# power1.net
KiCad netlist of a schematic drawn in Altium Designer
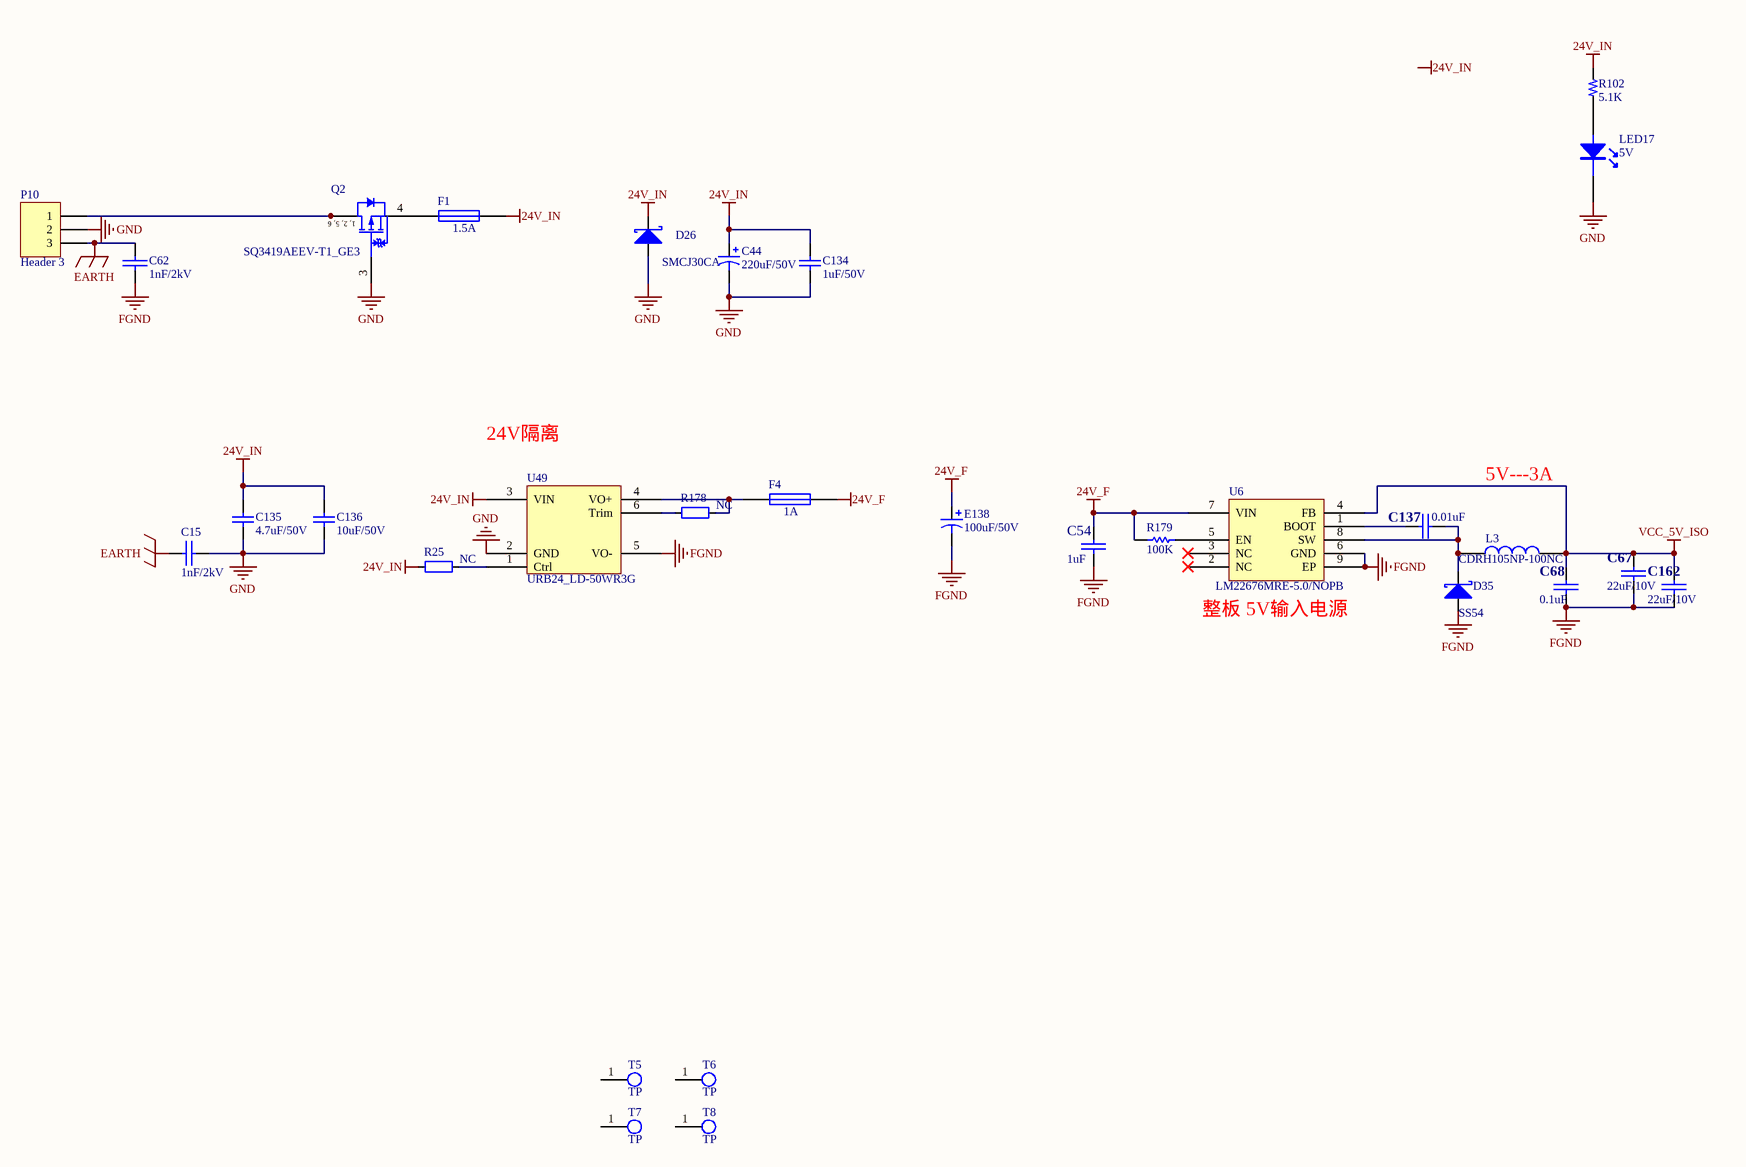
[diagram p0: power1.SchDoc]

(export (version "E")
  (design (tool "Eeschema 10.0.6"))
  (components
    (comp (ref "C15")
      (value "1nF/2kV")
      (footprint "1206C")
      (description "Capacitor")
      (libsource (lib "*") (part "CAP"))
    )
    (comp (ref "C44")
      (value "220uF/50V")
      (footprint "Φ10×10")
      (description "Polarized Capacitor (Radial)")
      (fields (field (name "PUBLISHER") "Altium Limited"))
      (libsource (lib "Miscellaneous Devices") (part "Cap Pol1"))
    )
    (comp (ref "C54")
      (value "1uF")
      (footprint "0603C")
      (description "Capacitor")
      (libsource (lib "*") (part "CAP"))
    )
    (comp (ref "C62")
      (value "1nF/2kV")
      (footprint "1206C")
      (description "Capacitor")
      (libsource (lib "*") (part "CAP"))
    )
    (comp (ref "C67")
      (value "22uF/10V")
      (footprint "1210C")
      (description "Capacitor")
      (libsource (lib "*") (part "CAP"))
    )
    (comp (ref "C68")
      (value "0.1uF")
      (footprint "0603C")
      (description "Capacitor")
      (libsource (lib "*") (part "CAP"))
    )
    (comp (ref "C134")
      (value "1uF/50V")
      (footprint "1210C")
      (description "Capacitor")
      (fields (field (name "PUBLISHER") "Altium Limited"))
      (libsource (lib "Miscellaneous Devices") (part "Cap"))
    )
    (comp (ref "C135")
      (value "4.7uF/50V")
      (footprint "1210C")
      (description "Capacitor")
      (fields (field (name "PUBLISHER") "Altium Limited"))
      (libsource (lib "Miscellaneous Devices") (part "Cap"))
    )
    (comp (ref "C136")
      (value "10uF/50V")
      (footprint "1210C")
      (description "Capacitor")
      (fields (field (name "PUBLISHER") "Altium Limited"))
      (libsource (lib "Miscellaneous Devices") (part "Cap"))
    )
    (comp (ref "C137")
      (value "0.01uF")
      (footprint "0603C")
      (description "Capacitor")
      (libsource (lib "*") (part "CAP"))
    )
    (comp (ref "C162")
      (value "22uF/10V")
      (footprint "1210C")
      (description "Capacitor")
      (libsource (lib "*") (part "CAP"))
    )
    (comp (ref "D26")
      (value "SMCJ30CA")
      (footprint "SMC")
      (description "Schottky Diode")
      (libsource (lib "*") (part "DIODE S"))
    )
    (comp (ref "D35")
      (value "SS54")
      (footprint "SMC")
      (description "Schottky Diode")
      (libsource (lib "*") (part "DIODE S"))
    )
    (comp (ref "E138")
      (value "100uF/50V")
      (footprint "Φ10×10")
      (description "Polarized Capacitor (Radial)")
      (fields (field (name "PUBLISHER") "Altium Limited"))
      (libsource (lib "Miscellaneous Devices") (part "Cap Pol1"))
    )
    (comp (ref "F1")
      (value "1.5A")
      (footprint "1812-F")
      (description "Fuse")
      (fields (field (name "PUBLISHER") "Altium Limited"))
      (libsource (lib "Miscellaneous Devices") (part "Fuse 1"))
    )
    (comp (ref "F4")
      (value "1A")
      (footprint "1812-F")
      (description "Fuse")
      (fields (field (name "PUBLISHER") "Altium Limited"))
      (libsource (lib "Miscellaneous Devices") (part "Fuse 1"))
    )
    (comp (ref "L3") (value "CDRH105NP-100NC") (footprint "CDRH105") (libsource (lib "*") (part "INDUCTOR")))
    (comp (ref "LED17") (value "5V") (footprint "0603LED") (libsource (lib "*") (part "LED")))
    (comp (ref "P10")
      (value "Header 3")
      (footprint "2ETYR-5.08-03P-14-100")
      (description "Header, 3-Pin")
      (fields (field (name "PUBLISHER") "Altium Limited"))
      (libsource (lib "Miscellaneous Connectors") (part "Header 3"))
    )
    (comp (ref "Q2")
      (value "SQ3419AEEV-T1_GE3")
      (footprint "VISH-TSOP-6_V")
      (description "Automotive P-Channel MOSFET, 6.9 A, 40 V, -55 to 175 degC, 6-Pin TSOP, RoHS, Tape and Reel")
      (fields (field (name "MANUFACTURER") "International Rectifier"))
      (libsource (lib "Bogen") (part "SQ3419AEEV-T1_GE3"))
    )
    (comp (ref "R25") (value "NC") (footprint "0603r") (libsource (lib "RC_M_D_00") (part "RES0603")))
    (comp (ref "R102")
      (value "5.1K")
      (footprint "0603R")
      (description "R")
      (libsource (lib "JRJ_1") (part "R"))
    )
    (comp (ref "R178") (value "NC") (footprint "0603r") (libsource (lib "RC_M_D_00") (part "RES0603")))
    (comp (ref "R179")
      (value "100K")
      (footprint "0603R")
      (description "Resistor")
      (fields (field (name "PUBLISHER") "Altium Limited"))
      (libsource (lib "Miscellaneous Devices") (part "Res1"))
    )
    (comp (ref "T5") (value "TP") (footprint "m2.5") (libsource (lib "Schlib_20110825") (part "TP")))
    (comp (ref "T6") (value "TP") (footprint "m2.5") (libsource (lib "Schlib_20110825") (part "TP")))
    (comp (ref "T7") (value "TP") (footprint "m2.5") (libsource (lib "Schlib_20110825") (part "TP")))
    (comp (ref "T8") (value "TP") (footprint "m2.5") (libsource (lib "Schlib_20110825") (part "TP")))
    (comp (ref "U6")
      (value "LM22676MRE-5.0/NOPB")
      (footprint "SOP127P600X168_HS-8N")
      (libsource (lib "Schlib1") (part "LM22676MR-5.0"))
    )
    (comp (ref "U49")
      (value "URB24_LD-50WR3G")
      (footprint "URB24_LD-50WR3G")
      (libsource (lib "Schlib1") (part "URB24_LD-50WR3G"))
    )
  )
  (nets
    (net (code "1") (name "24V_F") (class "Default")
      (node (ref "C54") (pin "2") (pinfunction "2_2") (pintype "passive"))
      (node (ref "E138") (pin "1") (pinfunction "1_1") (pintype "passive"))
      (node (ref "F4") (pin "2") (pinfunction "2_2") (pintype "passive"))
      (node (ref "R179") (pin "2") (pinfunction "2_2") (pintype "passive"))
      (node (ref "U6") (pin "7") (pinfunction "VIN_7") (pintype "passive"))
    )
    (net (code "2") (name "24V_IN") (class "Default")
      (node (ref "C134") (pin "2") (pinfunction "2_2") (pintype "passive"))
      (node (ref "C135") (pin "2") (pinfunction "2_2") (pintype "passive"))
      (node (ref "C136") (pin "2") (pinfunction "2_2") (pintype "passive"))
      (node (ref "C44") (pin "1") (pinfunction "1_1") (pintype "passive"))
      (node (ref "D26") (pin "2") (pinfunction "K_2") (pintype "passive"))
      (node (ref "F1") (pin "2") (pinfunction "2_2") (pintype "passive"))
      (node (ref "R102") (pin "2") (pintype "passive"))
      (node (ref "R25") (pin "1") (pinfunction "1_1") (pintype "passive"))
      (node (ref "U49") (pin "3") (pinfunction "VIN_3") (pintype "passive"))
    )
    (net (code "3") (name "EARTH") (class "Default")
      (node (ref "C15") (pin "2") (pinfunction "2_2") (pintype "passive"))
      (node (ref "C62") (pin "2") (pinfunction "2_2") (pintype "passive"))
      (node (ref "P10") (pin "3") (pinfunction "3_3") (pintype "passive"))
    )
    (net (code "4") (name "FGND") (class "Default")
      (node (ref "C162") (pin "2") (pinfunction "2_2") (pintype "passive"))
      (node (ref "C54") (pin "1") (pinfunction "1_1") (pintype "passive"))
      (node (ref "C62") (pin "1") (pinfunction "1_1") (pintype "passive"))
      (node (ref "C67") (pin "2") (pinfunction "2_2") (pintype "passive"))
      (node (ref "C68") (pin "2") (pinfunction "2_2") (pintype "passive"))
      (node (ref "D35") (pin "1") (pinfunction "A_1") (pintype "passive"))
      (node (ref "E138") (pin "2") (pinfunction "2_2") (pintype "passive"))
      (node (ref "U49") (pin "5") (pinfunction "VO-_5") (pintype "passive"))
      (node (ref "U6") (pin "6") (pinfunction "GND_6") (pintype "passive"))
      (node (ref "U6") (pin "9") (pinfunction "EP_9") (pintype "passive"))
    )
    (net (code "5") (name "GND") (class "Default")
      (node (ref "C134") (pin "1") (pinfunction "1_1") (pintype "passive"))
      (node (ref "C135") (pin "1") (pinfunction "1_1") (pintype "passive"))
      (node (ref "C136") (pin "1") (pinfunction "1_1") (pintype "passive"))
      (node (ref "C15") (pin "1") (pinfunction "1_1") (pintype "passive"))
      (node (ref "C44") (pin "2") (pinfunction "2_2") (pintype "passive"))
      (node (ref "D26") (pin "1") (pinfunction "A_1") (pintype "passive"))
      (node (ref "LED17") (pin "2") (pinfunction "2_2") (pintype "passive"))
      (node (ref "P10") (pin "2") (pinfunction "2_2") (pintype "passive"))
      (node (ref "Q2") (pin "3") (pinfunction "G_3") (pintype "passive"))
      (node (ref "U49") (pin "2") (pinfunction "GND_2") (pintype "passive"))
    )
    (net (code "6") (name "Net-(D35-K)") (class "Default")
      (node (ref "C137") (pin "1") (pinfunction "1_1") (pintype "passive"))
      (node (ref "D35") (pin "2") (pinfunction "K_2") (pintype "passive"))
      (node (ref "L3") (pin "1") (pinfunction "1_1") (pintype "passive"))
      (node (ref "U6") (pin "8") (pinfunction "SW_8") (pintype "passive"))
    )
    (net (code "7") (name "Net-(LED17-Pad1)") (class "Default")
      (node (ref "LED17") (pin "1") (pinfunction "1_1") (pintype "passive"))
      (node (ref "R102") (pin "1") (pintype "passive"))
    )
    (net (code "8") (name "Net-(P10-Pad1)") (class "Default")
      (node (ref "P10") (pin "1") (pinfunction "1_1") (pintype "passive"))
      (node (ref "Q2") (pin "1") (pinfunction "D_1") (pintype "passive"))
      (node (ref "Q2") (pin "2") (pinfunction "D_2") (pintype "passive"))
      (node (ref "Q2") (pin "5") (pinfunction "D_5") (pintype "passive"))
      (node (ref "Q2") (pin "6") (pinfunction "D_6") (pintype "passive"))
    )
    (net (code "9") (name "Net-(Q2-S)") (class "Default")
      (node (ref "F1") (pin "1") (pinfunction "1_1") (pintype "passive"))
      (node (ref "Q2") (pin "4") (pinfunction "S_4") (pintype "passive"))
    )
    (net (code "10") (name "Net-(U6-BOOT)") (class "Default")
      (node (ref "C137") (pin "2") (pinfunction "2_2") (pintype "passive"))
      (node (ref "U6") (pin "1") (pinfunction "BOOT_1") (pintype "passive"))
    )
    (net (code "11") (name "Net-(U6-EN)") (class "Default")
      (node (ref "R179") (pin "1") (pinfunction "1_1") (pintype "passive"))
      (node (ref "U6") (pin "5") (pinfunction "EN_5") (pintype "passive"))
    )
    (net (code "12") (name "Net-(U49-Ctrl)") (class "Default")
      (node (ref "R25") (pin "2") (pinfunction "2_2") (pintype "passive"))
      (node (ref "U49") (pin "1") (pinfunction "Ctrl_1") (pintype "passive"))
    )
    (net (code "13") (name "Net-(U49-Trim)") (class "Default")
      (node (ref "R178") (pin "1") (pinfunction "1_1") (pintype "passive"))
      (node (ref "U49") (pin "6") (pinfunction "Trim_6") (pintype "passive"))
    )
    (net (code "14") (name "Net-(U49-VO+)") (class "Default")
      (node (ref "F4") (pin "1") (pinfunction "1_1") (pintype "passive"))
      (node (ref "R178") (pin "2") (pinfunction "2_2") (pintype "passive"))
      (node (ref "U49") (pin "4") (pinfunction "VO+_4") (pintype "passive"))
    )
    (net (code "15") (name "VCC_5V_ISO") (class "Default")
      (node (ref "C162") (pin "1") (pinfunction "1_1") (pintype "passive"))
      (node (ref "C67") (pin "1") (pinfunction "1_1") (pintype "passive"))
      (node (ref "C68") (pin "1") (pinfunction "1_1") (pintype "passive"))
      (node (ref "L3") (pin "2") (pinfunction "2_2") (pintype "passive"))
      (node (ref "U6") (pin "4") (pinfunction "FB_4") (pintype "passive"))
    )
    (net (code "16") (name "unconnected-(T5-Pad1)") (class "Default")
      (node (ref "T5") (pin "1") (pintype "passive"))
    )
    (net (code "17") (name "unconnected-(T6-Pad1)") (class "Default")
      (node (ref "T6") (pin "1") (pintype "passive"))
    )
    (net (code "18") (name "unconnected-(T7-Pad1)") (class "Default")
      (node (ref "T7") (pin "1") (pintype "passive"))
    )
    (net (code "19") (name "unconnected-(T8-Pad1)") (class "Default")
      (node (ref "T8") (pin "1") (pintype "passive"))
    )
    (net (code "20") (name "unconnected-(U6-NC-Pad2)") (class "Default")
      (node (ref "U6") (pin "2") (pinfunction "NC_2") (pintype "passive+no_connect"))
    )
    (net (code "21") (name "unconnected-(U6-NC-Pad3)") (class "Default")
      (node (ref "U6") (pin "3") (pinfunction "NC_3") (pintype "passive+no_connect"))
    )
  )
)
